# PongSat_v3r5.net
KiCad netlist of a schematic drawn in EAGLE
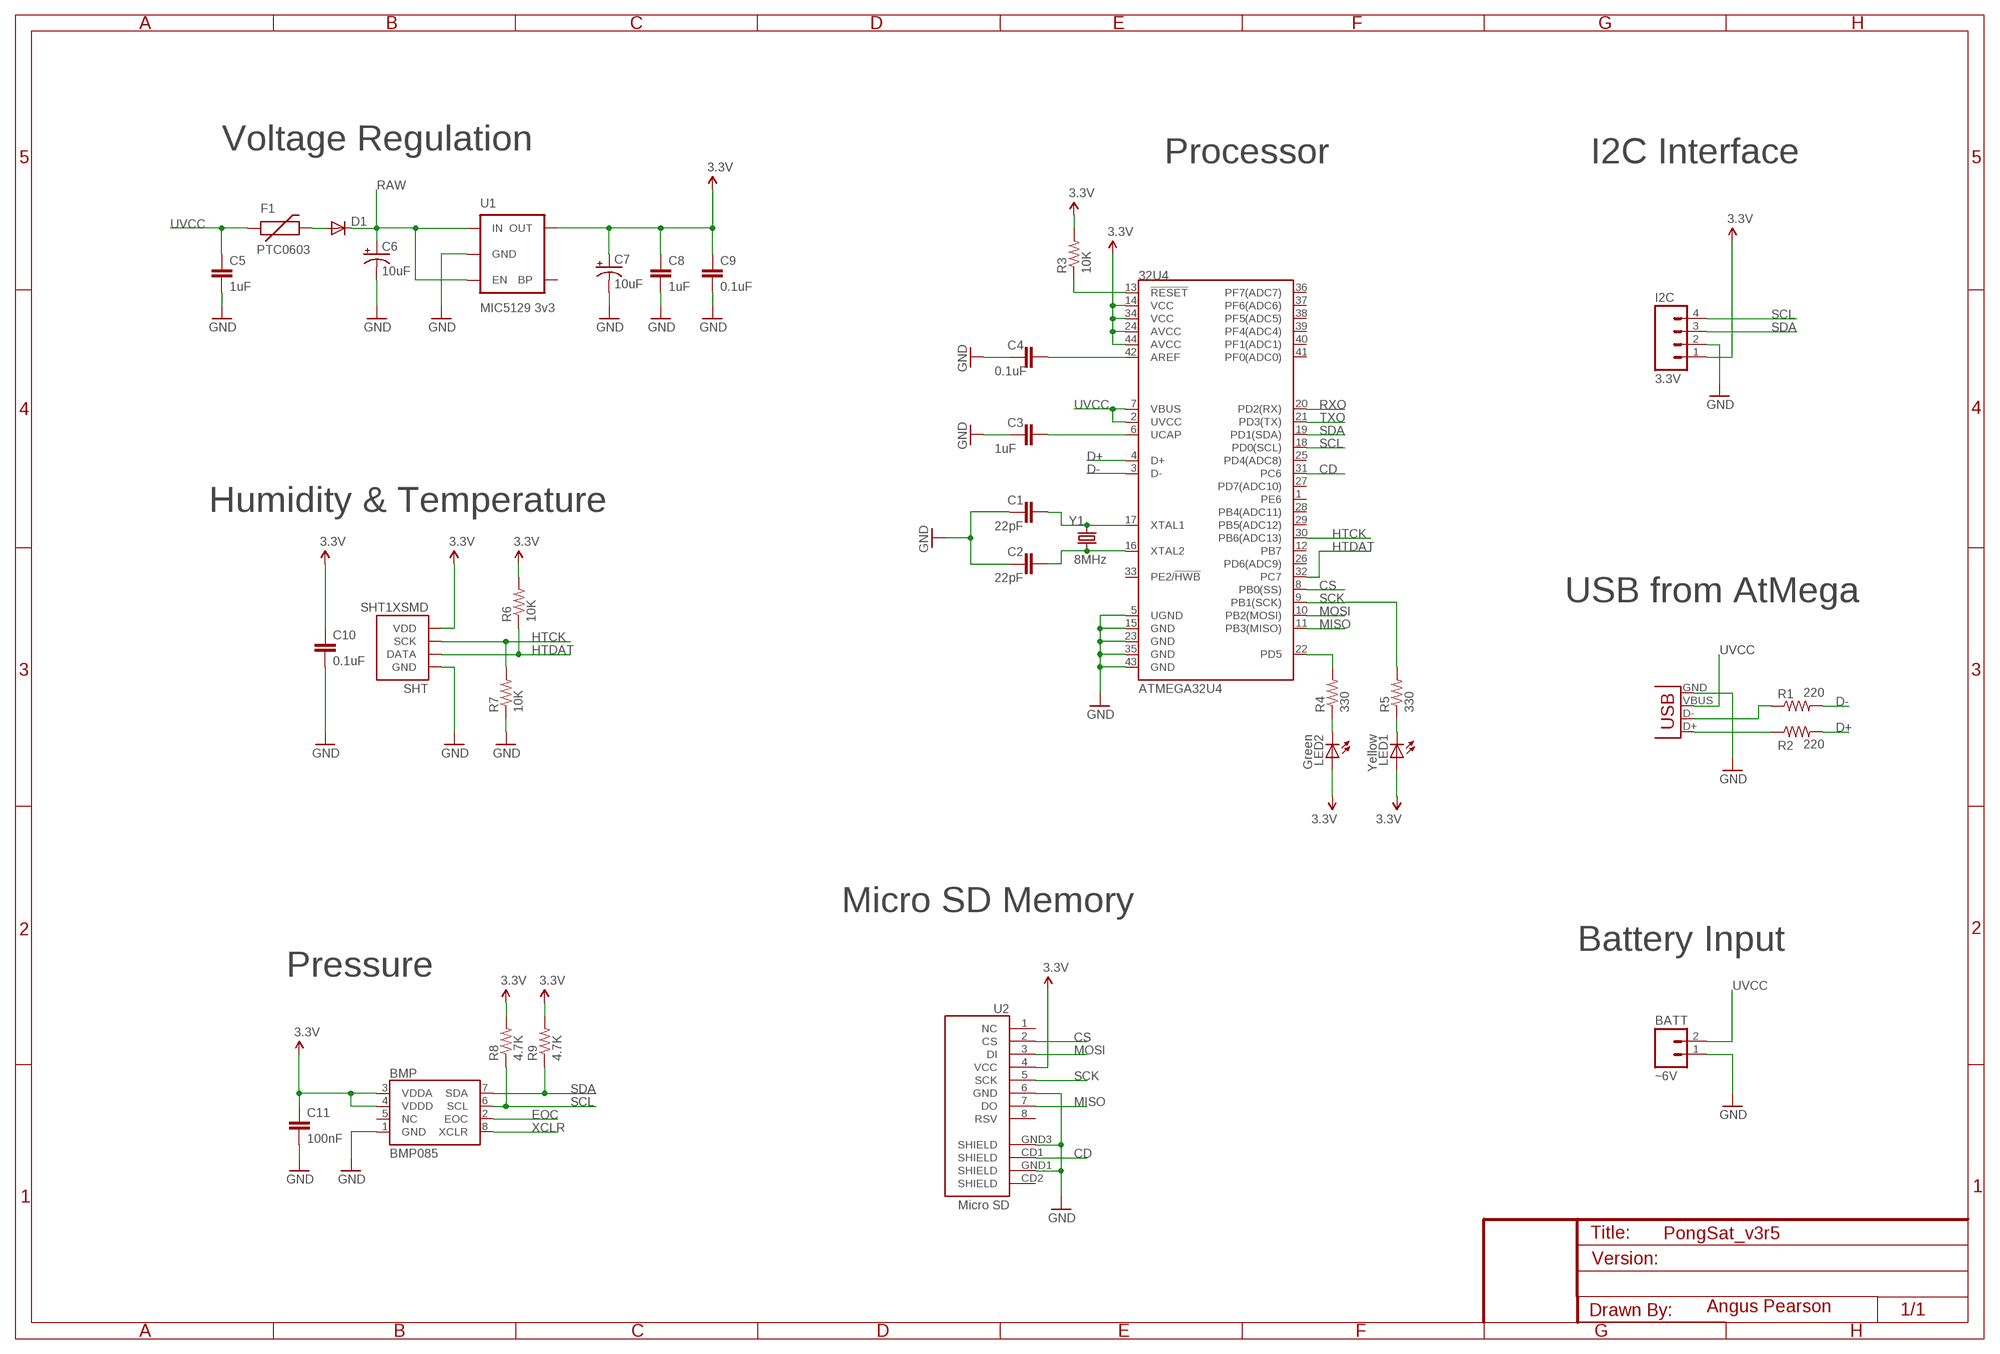
[diagram p0: schematic, sheet 1]

(export (version "E")
  (design (tool "Eeschema 10.0.6"))
  (components
    (comp (ref "32U4")
      (value "ATMEGA32U4")
      (footprint "eagle-import:QFN-44-NOPAD")
      (libsource (lib "eagle-import") (part "ATMEGA32U4QFN2"))
    )
    (comp (ref "BATT")
      (value "~6V")
      (footprint "eagle-import:1X02")
      (libsource (lib "eagle-import") (part "M02PTH"))
    )
    (comp (ref "BMP")
      (value "BMP085")
      (footprint "eagle-import:BMP085")
      (libsource (lib "eagle-import") (part "BMP085"))
    )
    (comp (ref "C1")
      (value "22pF")
      (footprint "eagle-import:0402-CAP")
      (libsource (lib "eagle-import") (part "CAP0402-CAP"))
    )
    (comp (ref "C2")
      (value "22pF")
      (footprint "eagle-import:0402-CAP")
      (libsource (lib "eagle-import") (part "CAP0402-CAP"))
    )
    (comp (ref "C3")
      (value "1uF")
      (footprint "eagle-import:0402-CAP")
      (libsource (lib "eagle-import") (part "CAP0402-CAP"))
    )
    (comp (ref "C4")
      (value "0.1uF")
      (footprint "eagle-import:0402-CAP")
      (libsource (lib "eagle-import") (part "CAP0402-CAP"))
    )
    (comp (ref "C5")
      (value "1uF")
      (footprint "eagle-import:0402-CAP")
      (libsource (lib "eagle-import") (part "CAP0402-CAP"))
    )
    (comp (ref "C6")
      (value "10uF")
      (footprint "eagle-import:EIA3216-KIT")
      (libsource (lib "eagle-import") (part "CAP_POL1206-KIT"))
    )
    (comp (ref "C7")
      (value "10uF")
      (footprint "eagle-import:EIA3216-KIT")
      (libsource (lib "eagle-import") (part "CAP_POL1206-KIT"))
    )
    (comp (ref "C8")
      (value "1uF")
      (footprint "eagle-import:0402-CAP")
      (libsource (lib "eagle-import") (part "CAP0402-CAP"))
    )
    (comp (ref "C9")
      (value "0.1uF")
      (footprint "eagle-import:0402-CAP")
      (libsource (lib "eagle-import") (part "CAP0402-CAP"))
    )
    (comp (ref "C10")
      (value "0.1uF")
      (footprint "eagle-import:0402-CAP")
      (libsource (lib "eagle-import") (part "CAP0402-CAP"))
    )
    (comp (ref "C11")
      (value "100nF")
      (footprint "eagle-import:0402-CAP")
      (libsource (lib "eagle-import") (part "CAP0402-CAP"))
    )
    (comp (ref "D1")
      (value "DIODESOT23")
      (footprint "eagle-import:SOT23-3")
      (libsource (lib "eagle-import") (part "DIODESOT23"))
    )
    (comp (ref "F1")
      (value "PTC0603")
      (footprint "eagle-import:0603")
      (libsource (lib "eagle-import") (part "PTC0603"))
    )
    (comp (ref "I2C")
      (value "3.3V")
      (footprint "eagle-import:1X04")
      (libsource (lib "eagle-import") (part "M04PTH"))
    )
    (comp (ref "LED1")
      (value "Yellow")
      (footprint "eagle-import:LED-0603")
      (libsource (lib "eagle-import") (part "LED0603"))
    )
    (comp (ref "LED2")
      (value "Green")
      (footprint "eagle-import:LED-0603")
      (libsource (lib "eagle-import") (part "LED0603"))
    )
    (comp (ref "R1")
      (value "220")
      (footprint "eagle-import:0402-RES")
      (libsource (lib "eagle-import") (part "RESISTOR0402-RES"))
    )
    (comp (ref "R2")
      (value "220")
      (footprint "eagle-import:0402-RES")
      (libsource (lib "eagle-import") (part "RESISTOR0402-RES"))
    )
    (comp (ref "R3")
      (value "10K")
      (footprint "eagle-import:0402-RES")
      (libsource (lib "eagle-import") (part "RESISTOR0402-RES"))
    )
    (comp (ref "R4")
      (value "330")
      (footprint "eagle-import:0402-RES")
      (libsource (lib "eagle-import") (part "RESISTOR0402-RES"))
    )
    (comp (ref "R5")
      (value "330")
      (footprint "eagle-import:0402-RES")
      (libsource (lib "eagle-import") (part "RESISTOR0402-RES"))
    )
    (comp (ref "R6")
      (value "10K")
      (footprint "eagle-import:0402-RES")
      (libsource (lib "eagle-import") (part "RESISTOR0402-RES"))
    )
    (comp (ref "R7")
      (value "10K")
      (footprint "eagle-import:0402-RES")
      (libsource (lib "eagle-import") (part "RESISTOR0402-RES"))
    )
    (comp (ref "R8")
      (value "4.7K")
      (footprint "eagle-import:0402-RES")
      (libsource (lib "eagle-import") (part "RESISTOR0402-RES"))
    )
    (comp (ref "R9")
      (value "4.7K")
      (footprint "eagle-import:0402-RES")
      (libsource (lib "eagle-import") (part "RESISTOR0402-RES"))
    )
    (comp (ref "SHT")
      (value "SHT1XSMD")
      (footprint "eagle-import:SHT1X")
      (libsource (lib "eagle-import") (part "SHT1XSMD"))
    )
    (comp (ref "U1")
      (value "MIC5129 3v3")
      (footprint "eagle-import:SOT23-5")
      (libsource (lib "eagle-import") (part "V_REG_MIC5219SMD"))
    )
    (comp (ref "U2")
      (value "Micro SD")
      (footprint "eagle-import:MICRO-SD-SOCKET-PP")
      (libsource (lib "eagle-import") (part "USD-SOCKETNEW"))
    )
    (comp (ref "X1")
      (value "USB-MICROB")
      (footprint "eagle-import:USB-MICROB")
      (libsource (lib "eagle-import") (part "USB-MICROB"))
    )
    (comp (ref "Y1")
      (value "8MHz")
      (footprint "eagle-import:CRYSTAL-SMD-5X3")
      (libsource (lib "eagle-import") (part "CRYSTAL5X3"))
    )
  )
  (nets
    (net (code "1") (name "/CD") (class "Default")
      (node (ref "32U4") (pin "31") (pinfunction "PC6_31") (pintype "bidirectional"))
      (node (ref "U2") (pin "CD1") (pinfunction "SHIELD_CD1") (pintype "bidirectional"))
    )
    (net (code "2") (name "/CS") (class "Default")
      (node (ref "32U4") (pin "8") (pinfunction "PB0(SS)_8") (pintype "bidirectional"))
      (node (ref "U2") (pin "2") (pinfunction "CS_2") (pintype "bidirectional"))
    )
    (net (code "3") (name "/D+") (class "Default")
      (node (ref "32U4") (pin "4") (pinfunction "D+_4") (pintype "bidirectional"))
      (node (ref "R2") (pin "2") (pinfunction "2_2") (pintype "passive"))
    )
    (net (code "4") (name "/D-") (class "Default")
      (node (ref "32U4") (pin "3") (pinfunction "D-_3") (pintype "bidirectional"))
      (node (ref "R1") (pin "2") (pinfunction "2_2") (pintype "passive"))
    )
    (net (code "5") (name "/EOC") (class "Default")
      (node (ref "BMP") (pin "2") (pinfunction "EOC_2") (pintype "output"))
    )
    (net (code "6") (name "/HTCK") (class "Default")
      (node (ref "32U4") (pin "30") (pinfunction "PB6(ADC13)_30") (pintype "bidirectional"))
      (node (ref "R7") (pin "2") (pinfunction "2_2") (pintype "passive"))
      (node (ref "SHT") (pin "3") (pinfunction "SCK_3") (pintype "input"))
    )
    (net (code "7") (name "/HTDAT") (class "Default")
      (node (ref "32U4") (pin "32") (pinfunction "PC7_32") (pintype "bidirectional"))
      (node (ref "R6") (pin "1") (pinfunction "1_1") (pintype "passive"))
      (node (ref "SHT") (pin "2") (pinfunction "DATA_2") (pintype "bidirectional"))
    )
    (net (code "8") (name "/MISO") (class "Default")
      (node (ref "32U4") (pin "11") (pinfunction "PB3(MISO)_11") (pintype "bidirectional"))
      (node (ref "U2") (pin "7") (pinfunction "DO_7") (pintype "bidirectional"))
    )
    (net (code "9") (name "/MOSI") (class "Default")
      (node (ref "32U4") (pin "10") (pinfunction "PB2(MOSI)_10") (pintype "bidirectional"))
      (node (ref "U2") (pin "3") (pinfunction "DI_3") (pintype "bidirectional"))
    )
    (net (code "10") (name "/RAW") (class "Default")
      (node (ref "C6") (pin "A") (pinfunction "+_A") (pintype "passive"))
      (node (ref "D1") (pin "3") (pinfunction "C_3") (pintype "passive"))
      (node (ref "U1") (pin "1") (pinfunction "IN_1") (pintype "input"))
      (node (ref "U1") (pin "3") (pinfunction "EN_3") (pintype "input"))
    )
    (net (code "11") (name "/RXO") (class "Default")
      (node (ref "32U4") (pin "20") (pinfunction "PD2(RX)_20") (pintype "bidirectional"))
    )
    (net (code "12") (name "/SCK") (class "Default")
      (node (ref "32U4") (pin "9") (pinfunction "PB1(SCK)_9") (pintype "bidirectional"))
      (node (ref "R5") (pin "2") (pinfunction "2_2") (pintype "passive"))
      (node (ref "U2") (pin "5") (pinfunction "SCK_5") (pintype "bidirectional"))
    )
    (net (code "13") (name "/SCL") (class "Default")
      (node (ref "32U4") (pin "18") (pinfunction "PD0(SCL)_18") (pintype "bidirectional"))
      (node (ref "BMP") (pin "6") (pinfunction "SCL_6") (pintype "input"))
      (node (ref "I2C") (pin "4") (pinfunction "4_4") (pintype "passive"))
      (node (ref "R8") (pin "1") (pinfunction "1_1") (pintype "passive"))
    )
    (net (code "14") (name "/SDA") (class "Default")
      (node (ref "32U4") (pin "19") (pinfunction "PD1(SDA)_19") (pintype "bidirectional"))
      (node (ref "BMP") (pin "7") (pinfunction "SDA_7") (pintype "bidirectional"))
      (node (ref "I2C") (pin "3") (pinfunction "3_3") (pintype "passive"))
      (node (ref "R9") (pin "1") (pinfunction "1_1") (pintype "passive"))
    )
    (net (code "15") (name "/TXO") (class "Default")
      (node (ref "32U4") (pin "21") (pinfunction "PD3(TX)_21") (pintype "bidirectional"))
    )
    (net (code "16") (name "/UVCC") (class "Default")
      (node (ref "32U4") (pin "2") (pinfunction "UVCC_2") (pintype "bidirectional"))
      (node (ref "32U4") (pin "7") (pinfunction "VBUS_7") (pintype "bidirectional"))
      (node (ref "BATT") (pin "2") (pinfunction "2_2") (pintype "passive"))
      (node (ref "C5") (pin "1") (pinfunction "1_1") (pintype "passive"))
      (node (ref "F1") (pin "1") (pinfunction "1_1") (pintype "bidirectional"))
      (node (ref "X1") (pin "VBUS") (pinfunction "VBUS_VBUS") (pintype "bidirectional"))
    )
    (net (code "17") (name "/XCLR") (class "Default")
      (node (ref "BMP") (pin "8") (pinfunction "XCLR_8") (pintype "input"))
    )
    (net (code "18") (name "3.3V") (class "Default")
      (node (ref "32U4") (pin "14") (pinfunction "VCC_14") (pintype "bidirectional"))
      (node (ref "32U4") (pin "24") (pinfunction "AVCC_24") (pintype "bidirectional"))
      (node (ref "32U4") (pin "34") (pinfunction "VCC_34") (pintype "bidirectional"))
      (node (ref "32U4") (pin "44") (pinfunction "AVCC_44") (pintype "bidirectional"))
      (node (ref "BMP") (pin "3") (pinfunction "VDDA_3") (pintype "power_in"))
      (node (ref "BMP") (pin "4") (pinfunction "VDDD_4") (pintype "power_in"))
      (node (ref "C10") (pin "1") (pinfunction "1_1") (pintype "passive"))
      (node (ref "C11") (pin "1") (pinfunction "1_1") (pintype "passive"))
      (node (ref "C7") (pin "A") (pinfunction "+_A") (pintype "passive"))
      (node (ref "C8") (pin "1") (pinfunction "1_1") (pintype "passive"))
      (node (ref "C9") (pin "1") (pinfunction "1_1") (pintype "passive"))
      (node (ref "I2C") (pin "1") (pinfunction "1_1") (pintype "passive"))
      (node (ref "LED1") (pin "A") (pinfunction "A_A") (pintype "passive"))
      (node (ref "LED2") (pin "A") (pinfunction "A_A") (pintype "passive"))
      (node (ref "R3") (pin "2") (pinfunction "2_2") (pintype "passive"))
      (node (ref "R6") (pin "2") (pinfunction "2_2") (pintype "passive"))
      (node (ref "R8") (pin "2") (pinfunction "2_2") (pintype "passive"))
      (node (ref "R9") (pin "2") (pinfunction "2_2") (pintype "passive"))
      (node (ref "SHT") (pin "4") (pinfunction "VDD_4") (pintype "power_in"))
      (node (ref "U1") (pin "5") (pinfunction "OUT_5") (pintype "passive"))
      (node (ref "U2") (pin "4") (pinfunction "VCC_4") (pintype "bidirectional"))
    )
    (net (code "19") (name "GND") (class "Default")
      (node (ref "32U4") (pin "15") (pinfunction "GND_15") (pintype "bidirectional"))
      (node (ref "32U4") (pin "23") (pinfunction "GND_23") (pintype "bidirectional"))
      (node (ref "32U4") (pin "35") (pinfunction "GND_35") (pintype "bidirectional"))
      (node (ref "32U4") (pin "43") (pinfunction "GND_43") (pintype "bidirectional"))
      (node (ref "32U4") (pin "5") (pinfunction "UGND_5") (pintype "bidirectional"))
      (node (ref "BATT") (pin "1") (pinfunction "1_1") (pintype "passive"))
      (node (ref "BMP") (pin "1") (pinfunction "GND_1") (pintype "power_in"))
      (node (ref "C1") (pin "1") (pinfunction "1_1") (pintype "passive"))
      (node (ref "C10") (pin "2") (pinfunction "2_2") (pintype "passive"))
      (node (ref "C11") (pin "2") (pinfunction "2_2") (pintype "passive"))
      (node (ref "C2") (pin "1") (pinfunction "1_1") (pintype "passive"))
      (node (ref "C3") (pin "1") (pinfunction "1_1") (pintype "passive"))
      (node (ref "C4") (pin "1") (pinfunction "1_1") (pintype "passive"))
      (node (ref "C5") (pin "2") (pinfunction "2_2") (pintype "passive"))
      (node (ref "C6") (pin "C") (pinfunction "-_C") (pintype "passive"))
      (node (ref "C7") (pin "C") (pinfunction "-_C") (pintype "passive"))
      (node (ref "C8") (pin "2") (pinfunction "2_2") (pintype "passive"))
      (node (ref "C9") (pin "2") (pinfunction "2_2") (pintype "passive"))
      (node (ref "I2C") (pin "2") (pinfunction "2_2") (pintype "passive"))
      (node (ref "R7") (pin "1") (pinfunction "1_1") (pintype "passive"))
      (node (ref "SHT") (pin "1") (pinfunction "GND_1") (pintype "power_in"))
      (node (ref "U1") (pin "2") (pinfunction "GND_2") (pintype "input"))
      (node (ref "U2") (pin "6") (pinfunction "GND_6") (pintype "bidirectional"))
      (node (ref "U2") (pin "GND1") (pinfunction "SHIELD_GND1") (pintype "bidirectional"))
      (node (ref "U2") (pin "GND3") (pinfunction "SHIELD_GND3") (pintype "bidirectional"))
      (node (ref "X1") (pin "GND") (pinfunction "GND_GND") (pintype "bidirectional"))
    )
    (net (code "20") (name "Net-(32U4-AREF)") (class "Default")
      (node (ref "32U4") (pin "42") (pinfunction "AREF_42") (pintype "bidirectional"))
      (node (ref "C4") (pin "2") (pinfunction "2_2") (pintype "passive"))
    )
    (net (code "21") (name "Net-(32U4-PD5)") (class "Default")
      (node (ref "32U4") (pin "22") (pinfunction "PD5_22") (pintype "bidirectional"))
      (node (ref "R4") (pin "2") (pinfunction "2_2") (pintype "passive"))
    )
    (net (code "22") (name "Net-(32U4-UCAP)") (class "Default")
      (node (ref "32U4") (pin "6") (pinfunction "UCAP_6") (pintype "bidirectional"))
      (node (ref "C3") (pin "2") (pinfunction "2_2") (pintype "passive"))
    )
    (net (code "23") (name "Net-(32U4-XTAL1)") (class "Default")
      (node (ref "32U4") (pin "17") (pinfunction "XTAL1_17") (pintype "bidirectional"))
      (node (ref "C1") (pin "2") (pinfunction "2_2") (pintype "passive"))
      (node (ref "Y1") (pin "3") (pinfunction "2_3") (pintype "passive"))
    )
    (net (code "24") (name "Net-(32U4-XTAL2)") (class "Default")
      (node (ref "32U4") (pin "16") (pinfunction "XTAL2_16") (pintype "bidirectional"))
      (node (ref "C2") (pin "2") (pinfunction "2_2") (pintype "passive"))
      (node (ref "Y1") (pin "1") (pinfunction "1_1") (pintype "passive"))
    )
    (net (code "25") (name "Net-(32U4-~{RESET})") (class "Default")
      (node (ref "32U4") (pin "13") (pinfunction "~{RESET}_13") (pintype "bidirectional"))
      (node (ref "R3") (pin "1") (pinfunction "1_1") (pintype "passive"))
    )
    (net (code "26") (name "Net-(D1-A)") (class "Default")
      (node (ref "D1") (pin "1") (pinfunction "A_1") (pintype "passive"))
      (node (ref "F1") (pin "2") (pinfunction "2_2") (pintype "bidirectional"))
    )
    (net (code "27") (name "Net-(LED1-PadC)") (class "Default")
      (node (ref "LED1") (pin "C") (pinfunction "C_C") (pintype "passive"))
      (node (ref "R5") (pin "1") (pinfunction "1_1") (pintype "passive"))
    )
    (net (code "28") (name "Net-(LED2-PadC)") (class "Default")
      (node (ref "LED2") (pin "C") (pinfunction "C_C") (pintype "passive"))
      (node (ref "R4") (pin "1") (pinfunction "1_1") (pintype "passive"))
    )
    (net (code "29") (name "Net-(R1-Pad1)") (class "Default")
      (node (ref "R1") (pin "1") (pinfunction "1_1") (pintype "passive"))
      (node (ref "X1") (pin "D-") (pinfunction "D-_D-") (pintype "bidirectional"))
    )
    (net (code "30") (name "Net-(R2-Pad1)") (class "Default")
      (node (ref "R2") (pin "1") (pinfunction "1_1") (pintype "passive"))
      (node (ref "X1") (pin "D+") (pinfunction "D+_D+") (pintype "bidirectional"))
    )
    (net (code "31") (name "unconnected-(32U4-PB4(ADC11)-Pad28)") (class "Default")
      (node (ref "32U4") (pin "28") (pinfunction "PB4(ADC11)_28") (pintype "bidirectional"))
    )
    (net (code "32") (name "unconnected-(32U4-PB5(ADC12)-Pad29)") (class "Default")
      (node (ref "32U4") (pin "29") (pinfunction "PB5(ADC12)_29") (pintype "bidirectional"))
    )
    (net (code "33") (name "unconnected-(32U4-PB7-Pad12)") (class "Default")
      (node (ref "32U4") (pin "12") (pinfunction "PB7_12") (pintype "bidirectional"))
    )
    (net (code "34") (name "unconnected-(32U4-PD4(ADC8)-Pad25)") (class "Default")
      (node (ref "32U4") (pin "25") (pinfunction "PD4(ADC8)_25") (pintype "bidirectional"))
    )
    (net (code "35") (name "unconnected-(32U4-PD6(ADC9)-Pad26)") (class "Default")
      (node (ref "32U4") (pin "26") (pinfunction "PD6(ADC9)_26") (pintype "bidirectional"))
    )
    (net (code "36") (name "unconnected-(32U4-PD7(ADC10)-Pad27)") (class "Default")
      (node (ref "32U4") (pin "27") (pinfunction "PD7(ADC10)_27") (pintype "bidirectional"))
    )
    (net (code "37") (name "unconnected-(32U4-PE2{slash}~{HWB}-Pad33)") (class "Default")
      (node (ref "32U4") (pin "33") (pinfunction "PE2/~{HWB}_33") (pintype "bidirectional"))
    )
    (net (code "38") (name "unconnected-(32U4-PE6-Pad1)") (class "Default")
      (node (ref "32U4") (pin "1") (pinfunction "PE6_1") (pintype "bidirectional"))
    )
    (net (code "39") (name "unconnected-(32U4-PF0(ADC0)-Pad41)") (class "Default")
      (node (ref "32U4") (pin "41") (pinfunction "PF0(ADC0)_41") (pintype "bidirectional"))
    )
    (net (code "40") (name "unconnected-(32U4-PF1(ADC1)-Pad40)") (class "Default")
      (node (ref "32U4") (pin "40") (pinfunction "PF1(ADC1)_40") (pintype "bidirectional"))
    )
    (net (code "41") (name "unconnected-(32U4-PF4(ADC4)-Pad39)") (class "Default")
      (node (ref "32U4") (pin "39") (pinfunction "PF4(ADC4)_39") (pintype "bidirectional"))
    )
    (net (code "42") (name "unconnected-(32U4-PF5(ADC5)-Pad38)") (class "Default")
      (node (ref "32U4") (pin "38") (pinfunction "PF5(ADC5)_38") (pintype "bidirectional"))
    )
    (net (code "43") (name "unconnected-(32U4-PF6(ADC6)-Pad37)") (class "Default")
      (node (ref "32U4") (pin "37") (pinfunction "PF6(ADC6)_37") (pintype "bidirectional"))
    )
    (net (code "44") (name "unconnected-(32U4-PF7(ADC7)-Pad36)") (class "Default")
      (node (ref "32U4") (pin "36") (pinfunction "PF7(ADC7)_36") (pintype "bidirectional"))
    )
    (net (code "45") (name "unconnected-(BMP-NC-Pad5)") (class "Default")
      (node (ref "BMP") (pin "5") (pinfunction "NC_5") (pintype "bidirectional"))
    )
    (net (code "46") (name "unconnected-(U1-BP-Pad4)") (class "Default")
      (node (ref "U1") (pin "4") (pinfunction "BP_4") (pintype "input"))
    )
    (net (code "47") (name "unconnected-(U2-NC-Pad1)") (class "Default")
      (node (ref "U2") (pin "1") (pinfunction "NC_1") (pintype "bidirectional"))
    )
    (net (code "48") (name "unconnected-(U2-RSV-Pad8)") (class "Default")
      (node (ref "U2") (pin "8") (pinfunction "RSV_8") (pintype "bidirectional"))
    )
    (net (code "49") (name "unconnected-(U2-SHIELD-PadCD2)") (class "Default")
      (node (ref "U2") (pin "CD2") (pinfunction "SHIELD_CD2") (pintype "bidirectional"))
    )
  )
)
